# 04_-_PCIE_MINI_1_PCIE.net
KiCad netlist of a schematic drawn in Altium Designer
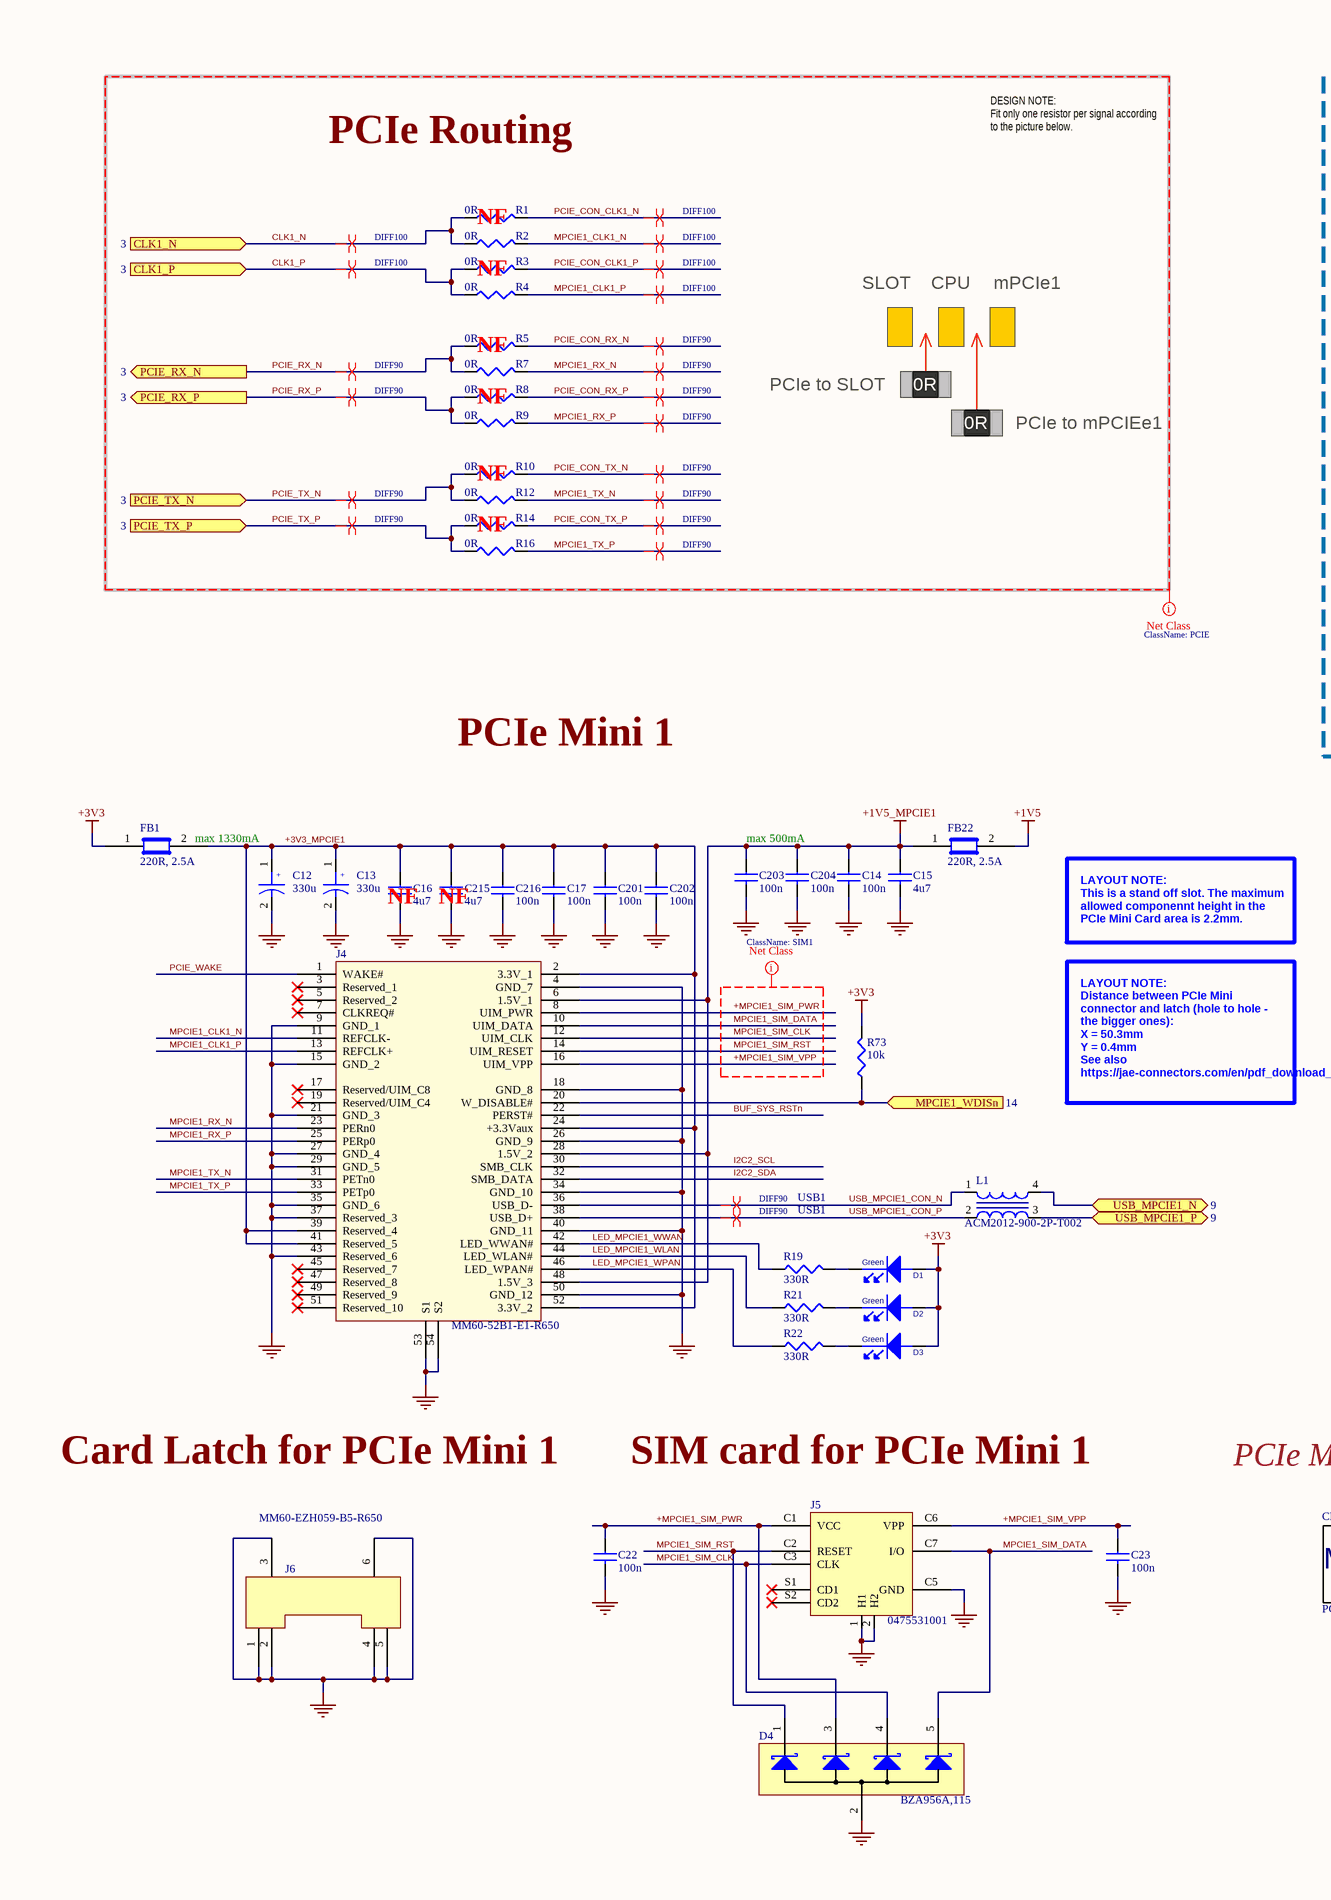
[diagram p0: [04] - PCIE MINI 1, PCIE.SchDoc, left]
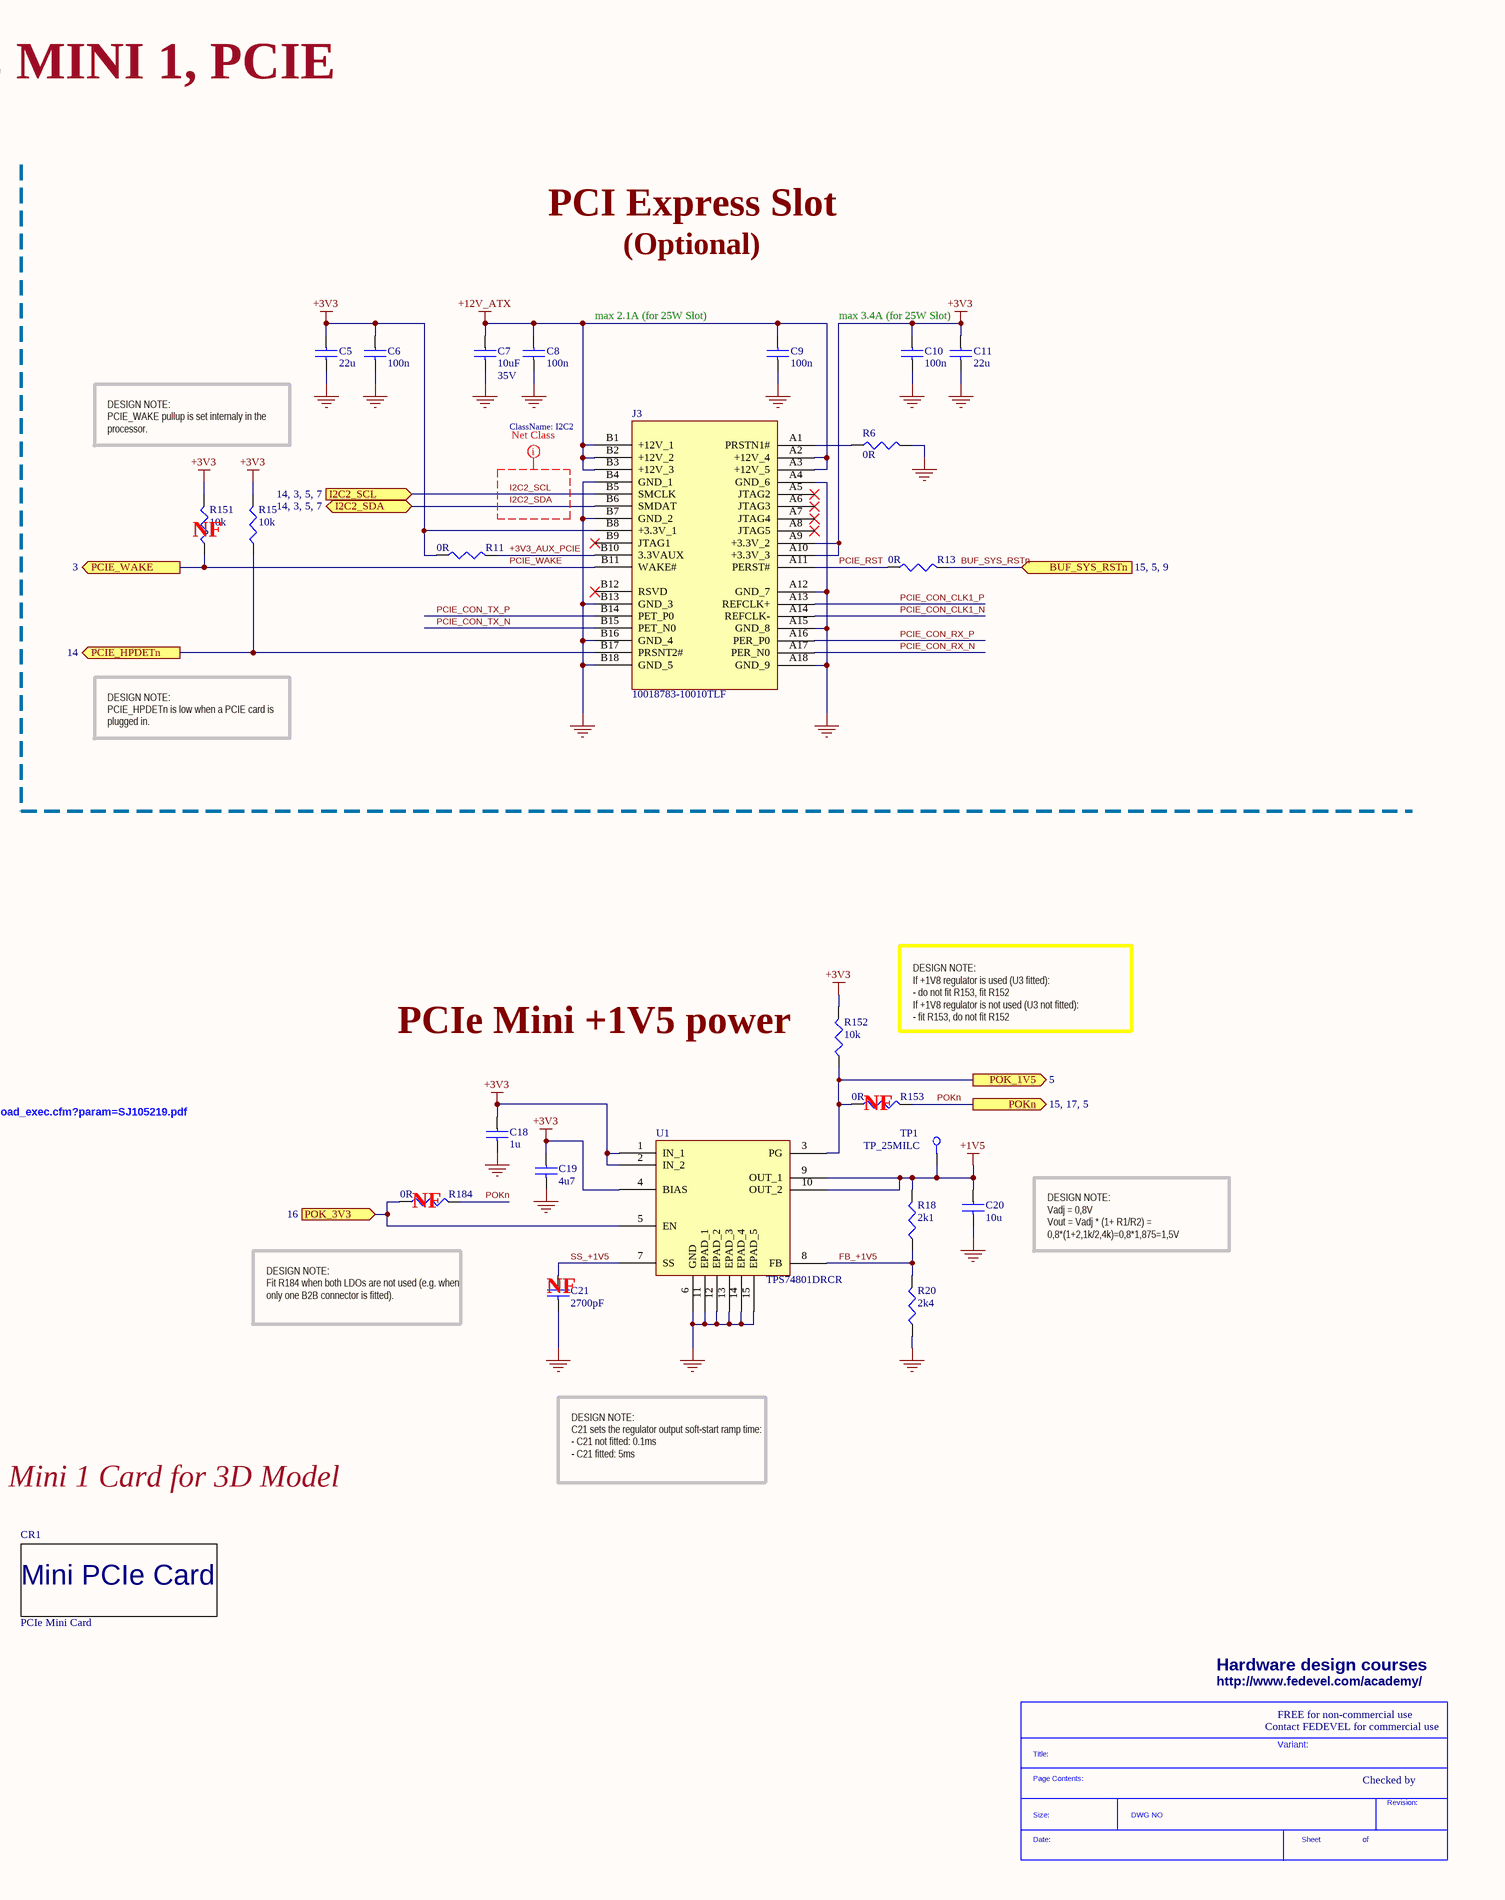
[diagram p1: [04] - PCIE MINI 1, PCIE.SchDoc, right]

(export (version "E")
  (design (tool "Eeschema 10.0.6"))
  (components
    (comp (ref "C5")
      (value "22u")
      (footprint "C0805")
      (description "CAP CER 22UF 16V 10% X5R 0805")
      (fields
        (field (name "MANUFACTURER") "TDK Corporation")
        (field (name "MANUFACTURER PART NUMBER") "C2012X5R1C226K")
        (field (name ".CHECKED PCB") "RF")
        (field (name ".CHECKED SCH") "RF")
      )
      (libsource (lib "Integrated_Library_RF_FEB_2012") (part "C2012X5R1C226K"))
    )
    (comp (ref "C6")
      (value "100n")
      (footprint "C0402")
      (description "CAP CER .10UF 50V X5R 10% 0402")
      (fields
        (field (name "MANUFACTURER") "TDK Corporation")
        (field (name "MANUFACTURER PART NUMBER") "C1005X5R1H104K")
      )
      (libsource (lib "Integrated_Library_RF_FEB_2012") (part "C1005X5R1H104K"))
    )
    (comp (ref "C7")
      (value "10uF")
      (footprint "C1206")
      (description "CAP CER 10UF 35V X5R 1206")
      (fields
        (field (name "MANUFACTURER") "Murata Electronics North America")
        (field (name "MANUFACTURER PART NUMBER") "GRM31CR6YA106KA12L")
        (field (name "VOLTAGE - RATED") "35V")
      )
      (libsource (lib "Integrated_Library_RF_FEB_2012") (part "GRM31CR6YA106KA12L"))
    )
    (comp (ref "C8")
      (value "100n")
      (footprint "C0402")
      (description "CAP CER .10UF 50V X5R 10% 0402")
      (fields
        (field (name "MANUFACTURER") "TDK Corporation")
        (field (name "MANUFACTURER PART NUMBER") "C1005X5R1H104K")
      )
      (libsource (lib "Integrated_Library_RF_FEB_2012") (part "C1005X5R1H104K"))
    )
    (comp (ref "C9")
      (value "100n")
      (footprint "C0402")
      (description "CAP CER .10UF 50V X5R 10% 0402")
      (fields
        (field (name "MANUFACTURER") "TDK Corporation")
        (field (name "MANUFACTURER PART NUMBER") "C1005X5R1H104K")
      )
      (libsource (lib "Integrated_Library_RF_FEB_2012") (part "C1005X5R1H104K"))
    )
    (comp (ref "C10")
      (value "100n")
      (footprint "C0402")
      (description "CAP CER .10UF 50V X5R 10% 0402")
      (fields
        (field (name "MANUFACTURER") "TDK Corporation")
        (field (name "MANUFACTURER PART NUMBER") "C1005X5R1H104K")
      )
      (libsource (lib "Integrated_Library_RF_FEB_2012") (part "C1005X5R1H104K"))
    )
    (comp (ref "C11")
      (value "22u")
      (footprint "C0805")
      (description "CAP CER 22UF 16V 10% X5R 0805")
      (fields
        (field (name "MANUFACTURER") "TDK Corporation")
        (field (name "MANUFACTURER PART NUMBER") "C2012X5R1C226K")
        (field (name ".CHECKED PCB") "RF")
        (field (name ".CHECKED SCH") "RF")
      )
      (libsource (lib "Integrated_Library_RF_FEB_2012") (part "C2012X5R1C226K"))
    )
    (comp (ref "C12")
      (value "330u")
      (footprint "C2917")
      (description "CAP TANT 330UF 6.3V 20% 2917")
      (fields
        (field (name "MANUFACTURER") "Kemet")
        (field (name "MANUFACTURER PART NUMBER") "T520D337M006ATE045")
        (field (name ".CREATOR") "MM")
        (field (name ".CHECKED PCB") "MM")
        (field (name ".CHECKED SCH") "RF, used by MM")
      )
      (libsource (lib "Integrated_Library_RF_FEB_2012") (part "T520D337M006ATE045"))
    )
    (comp (ref "C13")
      (value "330u")
      (footprint "C2917")
      (description "CAP TANT 330UF 6.3V 20% 2917")
      (fields
        (field (name "MANUFACTURER") "Kemet")
        (field (name "MANUFACTURER PART NUMBER") "T520D337M006ATE045")
        (field (name ".CREATOR") "MM")
        (field (name ".CHECKED PCB") "MM")
        (field (name ".CHECKED SCH") "RF, used by MM")
      )
      (libsource (lib "Integrated_Library_RF_FEB_2012") (part "T520D337M006ATE045"))
    )
    (comp (ref "C14")
      (value "100n")
      (footprint "C0402")
      (description "CAP CER .10UF 50V X5R 10% 0402")
      (fields
        (field (name "MANUFACTURER") "TDK Corporation")
        (field (name "MANUFACTURER PART NUMBER") "C1005X5R1H104K")
      )
      (libsource (lib "Integrated_Library_RF_FEB_2012") (part "C1005X5R1H104K"))
    )
    (comp (ref "C15")
      (value "4u7")
      (footprint "C0402")
      (description "CAP CER 4.7UF 10V 20% X5R 0402")
      (fields
        (field (name "MANUFACTURER") "TDK Corporation")
        (field (name "MANUFACTURER PART NUMBER") "C1005X5R1A475M")
        (field (name ".CHECKED PCB") "RF")
        (field (name ".CHECKED SCH") "RF")
      )
      (libsource (lib "Integrated_Library_RF_FEB_2012") (part "C1005X5R1A475M"))
    )
    (comp (ref "C16")
      (value "4u7")
      (footprint "C0402")
      (description "CAP CER 4.7UF 10V 20% X5R 0402")
      (fields
        (field (name "MANUFACTURER") "TDK Corporation")
        (field (name "MANUFACTURER PART NUMBER") "C1005X5R1A475M")
        (field (name ".CHECKED PCB") "RF")
        (field (name ".CHECKED SCH") "RF")
      )
      (libsource (lib "Integrated_Library_RF_FEB_2012") (part "C1005X5R1A475M"))
    )
    (comp (ref "C17")
      (value "100n")
      (footprint "C0402")
      (description "CAP CER .10UF 50V X5R 10% 0402")
      (fields
        (field (name "MANUFACTURER") "TDK Corporation")
        (field (name "MANUFACTURER PART NUMBER") "C1005X5R1H104K")
      )
      (libsource (lib "Integrated_Library_RF_FEB_2012") (part "C1005X5R1H104K"))
    )
    (comp (ref "C18")
      (value "1u")
      (footprint "C0402")
      (description "CAP CER 1.0UF 16V X5R 0402")
      (fields
        (field (name "MANUFACTURER") "TDK Corporation")
        (field (name "MANUFACTURER PART NUMBER") "C1005X5R1C105K")
      )
      (libsource (lib "Integrated_Library_RF_FEB_2012") (part "C1005X5R1C105K"))
    )
    (comp (ref "C19")
      (value "4u7")
      (footprint "C0402")
      (description "CAP CER 4.7UF 10V 20% X5R 0402")
      (fields
        (field (name "MANUFACTURER") "TDK Corporation")
        (field (name "MANUFACTURER PART NUMBER") "C1005X5R1A475M")
        (field (name ".CHECKED PCB") "RF")
        (field (name ".CHECKED SCH") "RF")
      )
      (libsource (lib "Integrated_Library_RF_FEB_2012") (part "C1005X5R1A475M"))
    )
    (comp (ref "C20")
      (value "10u")
      (footprint "C0603")
      (description "CAP CER 10UF 6.3V X5R 20% 0603")
      (fields
        (field (name "MANUFACTURER") "TDK Corporation")
        (field (name "MANUFACTURER PART NUMBER") "C1608X5R0J106M")
      )
      (libsource (lib "Integrated_Library_RF_FEB_2012") (part "C1608X5R0J106M"))
    )
    (comp (ref "C21")
      (value "2700pF")
      (footprint "C0402")
      (description "CAP CER 2700PF 50V 10% X7R 0402")
      (fields
        (field (name "MANUFACTURER") "Murata Electronics North America")
        (field (name "MANUFACTURER PART NUMBER") "GRM155R71H272KA01D")
        (field (name ".CHECKED PCB") "RF")
        (field (name ".CHECKED SCH") "RF")
      )
      (libsource (lib "Integrated_Library_RF_FEB_2012") (part "GRM155R71H272KA01D"))
    )
    (comp (ref "C22")
      (value "100n")
      (footprint "C0402")
      (description "CAP CER .10UF 50V X5R 10% 0402")
      (fields
        (field (name "MANUFACTURER") "TDK Corporation")
        (field (name "MANUFACTURER PART NUMBER") "C1005X5R1H104K")
      )
      (libsource (lib "Integrated_Library_RF_FEB_2012") (part "C1005X5R1H104K"))
    )
    (comp (ref "C23")
      (value "100n")
      (footprint "C0402")
      (description "CAP CER .10UF 50V X5R 10% 0402")
      (fields
        (field (name "MANUFACTURER") "TDK Corporation")
        (field (name "MANUFACTURER PART NUMBER") "C1005X5R1H104K")
      )
      (libsource (lib "Integrated_Library_RF_FEB_2012") (part "C1005X5R1H104K"))
    )
    (comp (ref "C201")
      (value "100n")
      (footprint "C0402")
      (description "CAP CER .10UF 50V X5R 10% 0402")
      (fields
        (field (name "MANUFACTURER") "TDK Corporation")
        (field (name "MANUFACTURER PART NUMBER") "C1005X5R1H104K")
      )
      (libsource (lib "Integrated_Library_RF_FEB_2012") (part "C1005X5R1H104K"))
    )
    (comp (ref "C202")
      (value "100n")
      (footprint "C0402")
      (description "CAP CER .10UF 50V X5R 10% 0402")
      (fields
        (field (name "MANUFACTURER") "TDK Corporation")
        (field (name "MANUFACTURER PART NUMBER") "C1005X5R1H104K")
      )
      (libsource (lib "Integrated_Library_RF_FEB_2012") (part "C1005X5R1H104K"))
    )
    (comp (ref "C203")
      (value "100n")
      (footprint "C0402")
      (description "CAP CER .10UF 50V X5R 10% 0402")
      (fields
        (field (name "MANUFACTURER") "TDK Corporation")
        (field (name "MANUFACTURER PART NUMBER") "C1005X5R1H104K")
      )
      (libsource (lib "Integrated_Library_RF_FEB_2012") (part "C1005X5R1H104K"))
    )
    (comp (ref "C204")
      (value "100n")
      (footprint "C0402")
      (description "CAP CER .10UF 50V X5R 10% 0402")
      (fields
        (field (name "MANUFACTURER") "TDK Corporation")
        (field (name "MANUFACTURER PART NUMBER") "C1005X5R1H104K")
      )
      (libsource (lib "Integrated_Library_RF_FEB_2012") (part "C1005X5R1H104K"))
    )
    (comp (ref "C215")
      (value "4u7")
      (footprint "C0402")
      (description "CAP CER 4.7UF 10V 20% X5R 0402")
      (fields
        (field (name "MANUFACTURER") "TDK Corporation")
        (field (name "MANUFACTURER PART NUMBER") "C1005X5R1A475M")
        (field (name ".CHECKED PCB") "RF")
        (field (name ".CHECKED SCH") "RF")
      )
      (libsource (lib "Integrated_Library_RF_FEB_2012") (part "C1005X5R1A475M"))
    )
    (comp (ref "C216")
      (value "100n")
      (footprint "C0402")
      (description "CAP CER .10UF 50V X5R 10% 0402")
      (fields
        (field (name "MANUFACTURER") "TDK Corporation")
        (field (name "MANUFACTURER PART NUMBER") "C1005X5R1H104K")
      )
      (libsource (lib "Integrated_Library_RF_FEB_2012") (part "C1005X5R1H104K"))
    )
    (comp (ref "CR1")
      (value "PCIe Mini Card")
      (footprint "Mini_PCIe_full card")
      (description "Card MIni PCIe")
      (fields (field (name ".CREATOR") "MM"))
      (libsource (lib "Integrated_Library_RF_FEB_2012") (part "Card_Mini_PCIe"))
    )
    (comp (ref "D1")
      (value "Green")
      (footprint "LED_0603")
      (description "LED SMARTLED GREEN 570NM 0603")
      (fields
        (field (name "MANUFACTURER") "OSRAM Opto Semiconductors Inc")
        (field (name "MANUFACTURER PART NUMBER") "LG L29K-G2J1-24-Z")
      )
      (libsource (lib "Integrated_Library_RF_FEB_2012") (part "LG L29K-G2J1-24-Z"))
    )
    (comp (ref "D2")
      (value "Green")
      (footprint "LED_0603")
      (description "LED SMARTLED GREEN 570NM 0603")
      (fields
        (field (name "MANUFACTURER") "OSRAM Opto Semiconductors Inc")
        (field (name "MANUFACTURER PART NUMBER") "LG L29K-G2J1-24-Z")
      )
      (libsource (lib "Integrated_Library_RF_FEB_2012") (part "LG L29K-G2J1-24-Z"))
    )
    (comp (ref "D3")
      (value "Green")
      (footprint "LED_0603")
      (description "LED SMARTLED GREEN 570NM 0603")
      (fields
        (field (name "MANUFACTURER") "OSRAM Opto Semiconductors Inc")
        (field (name "MANUFACTURER PART NUMBER") "LG L29K-G2J1-24-Z")
      )
      (libsource (lib "Integrated_Library_RF_FEB_2012") (part "LG L29K-G2J1-24-Z"))
    )
    (comp (ref "D4")
      (value "BZA956A,115")
      (footprint "SOT665")
      (description "TVS ZENER QUAD 5.6V SOT665")
      (fields
        (field (name "MANUFACTURER") "NXP Semiconductors")
        (field (name ".CREATOR") "MM")
        (field (name ".CHECKED PCB") "MM")
        (field (name ".CHECKED SCH") "MM")
      )
      (libsource (lib "Integrated_Library_RF_FEB_2012") (part "BZA956A,115"))
    )
    (comp (ref "FB1")
      (value "220R, 2.5A")
      (footprint "C0603")
      (description "FERRITE CHIP 220 OHM 2500MA 0603")
      (fields
        (field (name "MANUFACTURER") "Murata Electronics North America")
        (field (name "MANUFACTURER PART NUMBER") "BLM18SG221TN1D")
        (field (name ".CHECKED PCB") "RF")
        (field (name ".CHECKED SCH") "RF")
      )
      (libsource (lib "Integrated_Library_RF_FEB_2012") (part "BLM18SG221TN1D"))
    )
    (comp (ref "FB22")
      (value "220R, 2.5A")
      (footprint "C0603")
      (description "FERRITE CHIP 220 OHM 2500MA 0603")
      (fields
        (field (name "MANUFACTURER") "Murata Electronics North America")
        (field (name "MANUFACTURER PART NUMBER") "BLM18SG221TN1D")
        (field (name ".CHECKED PCB") "RF")
        (field (name ".CHECKED SCH") "RF")
      )
      (libsource (lib "Integrated_Library_RF_FEB_2012") (part "BLM18SG221TN1D"))
    )
    (comp (ref "J3")
      (value "10018783-10010TLF")
      (footprint "Mini_PCIe_36pin")
      (description "CONN PCI EXPRESS 36POS VERT PCB")
      (fields
        (field (name ".CREATOR") "MM")
        (field (name ".CHECKED PCB") "MM")
        (field (name ".CHECKED SCH") "MM")
      )
      (libsource (lib "Integrated_Library_RF_FEB_2012") (part "10018783-10010TLF"))
    )
    (comp (ref "J4")
      (value "MM60-52B1-E1-R650")
      (footprint "MINI_PCIE_52PIN_CARD_CON")
      (description "CONN MINI EXPRESS CARD 52POS SMD")
      (fields
        (field (name "MANUFACTURER") "JAE Electronics")
        (field (name ".CREATOR") "MM")
        (field (name ".CHECKED PCB") "MM")
        (field (name ".CHECKED SCH") "MM")
      )
      (libsource (lib "Integrated_Library_RF_FEB_2012") (part "MM60-52B1-E1-R650"))
    )
    (comp (ref "J5")
      (value "0475531001")
      (footprint "SIM_CARD_PUSH")
      (description "CONN CARD HOLDER SIM 6POS SMD")
      (fields
        (field (name "MANUFACTURER") "Molex Inc")
        (field (name ".CREATOR") "MM")
        (field (name ".CHECKED PCB") "MM")
        (field (name ".CHECKED SCH") "MM")
      )
      (libsource (lib "Integrated_Library_RF_FEB_2012") (part "0475531001"))
    )
    (comp (ref "J6")
      (value "MM60-EZH059-B5-R650")
      (footprint "MINI_PCIE_52PIN_CARD_LATCH")
      (description "CONN MINI EXPRESS CARD LATCH SMD")
      (fields
        (field (name "MANUFACTURER") "JAE Electronics")
        (field (name ".CREATOR") "MM")
        (field (name ".CHECKED PCB") "MM")
        (field (name ".CHECKED SCH") "MM")
      )
      (libsource (lib "Integrated_Library_RF_FEB_2012") (part "MM60-EZH059-B5-R650"))
    )
    (comp (ref "L1")
      (value "ACM2012-900-2P-T002")
      (footprint "ACM2012")
      (description "CHOKE COMM MODE 90 OHM .4A SMD")
      (fields
        (field (name "MANUFACTURER") "TDK Corporation")
        (field (name "TOLERANCE") "±1%")
        (field (name ".CHECKED PCB") "RF")
        (field (name ".CHECKED SCH") "RF")
      )
      (libsource (lib "Integrated_Library_RF_FEB_2012") (part "ACM2012-900-2P-T002"))
    )
    (comp (ref "R1")
      (value "0R")
      (footprint "R0402")
      (description "RES 0.0 OHM 1/16W 0402 SMD")
      (fields
        (field (name "MANUFACTURER") "Yageo")
        (field (name "MANUFACTURER PART NUMBER") "RC0402JR-070RL")
      )
      (libsource (lib "Integrated_Library_RF_FEB_2012") (part "RC0402JR-070RL"))
    )
    (comp (ref "R2")
      (value "0R")
      (footprint "R0402")
      (description "RES 0.0 OHM 1/16W 0402 SMD")
      (fields
        (field (name "MANUFACTURER") "Yageo")
        (field (name "MANUFACTURER PART NUMBER") "RC0402JR-070RL")
      )
      (libsource (lib "Integrated_Library_RF_FEB_2012") (part "RC0402JR-070RL"))
    )
    (comp (ref "R3")
      (value "0R")
      (footprint "R0402")
      (description "RES 0.0 OHM 1/16W 0402 SMD")
      (fields
        (field (name "MANUFACTURER") "Yageo")
        (field (name "MANUFACTURER PART NUMBER") "RC0402JR-070RL")
      )
      (libsource (lib "Integrated_Library_RF_FEB_2012") (part "RC0402JR-070RL"))
    )
    (comp (ref "R4")
      (value "0R")
      (footprint "R0402")
      (description "RES 0.0 OHM 1/16W 0402 SMD")
      (fields
        (field (name "MANUFACTURER") "Yageo")
        (field (name "MANUFACTURER PART NUMBER") "RC0402JR-070RL")
      )
      (libsource (lib "Integrated_Library_RF_FEB_2012") (part "RC0402JR-070RL"))
    )
    (comp (ref "R5")
      (value "0R")
      (footprint "R0402")
      (description "RES 0.0 OHM 1/16W 0402 SMD")
      (fields
        (field (name "MANUFACTURER") "Yageo")
        (field (name "MANUFACTURER PART NUMBER") "RC0402JR-070RL")
      )
      (libsource (lib "Integrated_Library_RF_FEB_2012") (part "RC0402JR-070RL"))
    )
    (comp (ref "R6")
      (value "0R")
      (footprint "R0402")
      (description "RES 0.0 OHM 1/16W 0402 SMD")
      (fields
        (field (name "MANUFACTURER") "Yageo")
        (field (name "MANUFACTURER PART NUMBER") "RC0402JR-070RL")
      )
      (libsource (lib "Integrated_Library_RF_FEB_2012") (part "RC0402JR-070RL"))
    )
    (comp (ref "R7")
      (value "0R")
      (footprint "R0402")
      (description "RES 0.0 OHM 1/16W 0402 SMD")
      (fields
        (field (name "MANUFACTURER") "Yageo")
        (field (name "MANUFACTURER PART NUMBER") "RC0402JR-070RL")
      )
      (libsource (lib "Integrated_Library_RF_FEB_2012") (part "RC0402JR-070RL"))
    )
    (comp (ref "R8")
      (value "0R")
      (footprint "R0402")
      (description "RES 0.0 OHM 1/16W 0402 SMD")
      (fields
        (field (name "MANUFACTURER") "Yageo")
        (field (name "MANUFACTURER PART NUMBER") "RC0402JR-070RL")
      )
      (libsource (lib "Integrated_Library_RF_FEB_2012") (part "RC0402JR-070RL"))
    )
    (comp (ref "R9")
      (value "0R")
      (footprint "R0402")
      (description "RES 0.0 OHM 1/16W 0402 SMD")
      (fields
        (field (name "MANUFACTURER") "Yageo")
        (field (name "MANUFACTURER PART NUMBER") "RC0402JR-070RL")
      )
      (libsource (lib "Integrated_Library_RF_FEB_2012") (part "RC0402JR-070RL"))
    )
    (comp (ref "R10")
      (value "0R")
      (footprint "R0402")
      (description "RES 0.0 OHM 1/16W 0402 SMD")
      (fields
        (field (name "MANUFACTURER") "Yageo")
        (field (name "MANUFACTURER PART NUMBER") "RC0402JR-070RL")
      )
      (libsource (lib "Integrated_Library_RF_FEB_2012") (part "RC0402JR-070RL"))
    )
    (comp (ref "R11")
      (value "0R")
      (footprint "R0402")
      (description "RES 0.0 OHM 1/16W 0402 SMD")
      (fields
        (field (name "MANUFACTURER") "Yageo")
        (field (name "MANUFACTURER PART NUMBER") "RC0402JR-070RL")
      )
      (libsource (lib "Integrated_Library_RF_FEB_2012") (part "RC0402JR-070RL"))
    )
    (comp (ref "R12")
      (value "0R")
      (footprint "R0402")
      (description "RES 0.0 OHM 1/16W 0402 SMD")
      (fields
        (field (name "MANUFACTURER") "Yageo")
        (field (name "MANUFACTURER PART NUMBER") "RC0402JR-070RL")
      )
      (libsource (lib "Integrated_Library_RF_FEB_2012") (part "RC0402JR-070RL"))
    )
    (comp (ref "R13")
      (value "0R")
      (footprint "R0402")
      (description "RES 0.0 OHM 1/16W 0402 SMD")
      (fields
        (field (name "MANUFACTURER") "Yageo")
        (field (name "MANUFACTURER PART NUMBER") "RC0402JR-070RL")
      )
      (libsource (lib "Integrated_Library_RF_FEB_2012") (part "RC0402JR-070RL"))
    )
    (comp (ref "R14")
      (value "0R")
      (footprint "R0402")
      (description "RES 0.0 OHM 1/16W 0402 SMD")
      (fields
        (field (name "MANUFACTURER") "Yageo")
        (field (name "MANUFACTURER PART NUMBER") "RC0402JR-070RL")
      )
      (libsource (lib "Integrated_Library_RF_FEB_2012") (part "RC0402JR-070RL"))
    )
    (comp (ref "R15")
      (value "10k")
      (footprint "R0402")
      (description "RES 10.0K OHM 1/16W 1% 0402 SMD")
      (fields
        (field (name "MANUFACTURER") "Yageo")
        (field (name "MANUFACTURER PART NUMBER") "RC0402FR-0710KL")
      )
      (libsource (lib "Integrated_Library_RF_FEB_2012") (part "RC0402FR-0710KL"))
    )
    (comp (ref "R16")
      (value "0R")
      (footprint "R0402")
      (description "RES 0.0 OHM 1/16W 0402 SMD")
      (fields
        (field (name "MANUFACTURER") "Yageo")
        (field (name "MANUFACTURER PART NUMBER") "RC0402JR-070RL")
      )
      (libsource (lib "Integrated_Library_RF_FEB_2012") (part "RC0402JR-070RL"))
    )
    (comp (ref "R18")
      (value "2k1")
      (footprint "R0402")
      (description "RES 2.10K OHM 1/16W 1% 0402 SMD")
      (fields
        (field (name "MANUFACTURER") "Vishay Dale")
        (field (name "MANUFACTURER PART NUMBER") "CRCW04022K10FKED")
        (field (name ".CREATOR") "MM")
        (field (name ".CHECKED PCB") "RF, used by MM")
        (field (name ".CHECKED SCH") "RF, used by MM")
      )
      (libsource (lib "Integrated_Library_RF_FEB_2012") (part "CRCW04022K10FKED"))
    )
    (comp (ref "R19")
      (value "330R")
      (footprint "R0402")
      (description "RES 330 OHM 1/16W 1% 0402 SMD")
      (fields
        (field (name "MANUFACTURER") "Vishay Dale")
        (field (name "MANUFACTURER PART NUMBER") "CRCW0402330RFKED")
        (field (name ".CHECKED PCB") "RF")
        (field (name ".CHECKED SCH") "RF")
      )
      (libsource (lib "Integrated_Library_RF_FEB_2012") (part "CRCW0402330RFKED"))
    )
    (comp (ref "R20")
      (value "2k4")
      (footprint "R0402")
      (description "RES 2.40K OHM 1/16W 1% 0402 SMD")
      (fields
        (field (name "MANUFACTURER") "Vishay Dale")
        (field (name "MANUFACTURER PART NUMBER") "CRCW04022K40FKED")
        (field (name ".CHECKED PCB") "RF")
        (field (name ".CHECKED SCH") "RF")
      )
      (libsource (lib "Integrated_Library_RF_FEB_2012") (part "CRCW04022K40FKED"))
    )
    (comp (ref "R21")
      (value "330R")
      (footprint "R0402")
      (description "RES 330 OHM 1/16W 1% 0402 SMD")
      (fields
        (field (name "MANUFACTURER") "Vishay Dale")
        (field (name "MANUFACTURER PART NUMBER") "CRCW0402330RFKED")
        (field (name ".CHECKED PCB") "RF")
        (field (name ".CHECKED SCH") "RF")
      )
      (libsource (lib "Integrated_Library_RF_FEB_2012") (part "CRCW0402330RFKED"))
    )
    (comp (ref "R22")
      (value "330R")
      (footprint "R0402")
      (description "RES 330 OHM 1/16W 1% 0402 SMD")
      (fields
        (field (name "MANUFACTURER") "Vishay Dale")
        (field (name "MANUFACTURER PART NUMBER") "CRCW0402330RFKED")
        (field (name ".CHECKED PCB") "RF")
        (field (name ".CHECKED SCH") "RF")
      )
      (libsource (lib "Integrated_Library_RF_FEB_2012") (part "CRCW0402330RFKED"))
    )
    (comp (ref "R73")
      (value "10k")
      (footprint "R0402")
      (description "RES 10.0K OHM 1/16W 1% 0402 SMD")
      (fields
        (field (name "MANUFACTURER") "Yageo")
        (field (name "MANUFACTURER PART NUMBER") "RC0402FR-0710KL")
      )
      (libsource (lib "Integrated_Library_RF_FEB_2012") (part "RC0402FR-0710KL"))
    )
    (comp (ref "R151")
      (value "10k")
      (footprint "R0402")
      (description "RES 10.0K OHM 1/16W 1% 0402 SMD")
      (fields
        (field (name "MANUFACTURER") "Yageo")
        (field (name "MANUFACTURER PART NUMBER") "RC0402FR-0710KL")
      )
      (libsource (lib "Integrated_Library_RF_FEB_2012") (part "RC0402FR-0710KL"))
    )
    (comp (ref "R152")
      (value "10k")
      (footprint "R0402")
      (description "RES 10.0K OHM 1/16W 1% 0402 SMD")
      (fields
        (field (name "MANUFACTURER") "Yageo")
        (field (name "MANUFACTURER PART NUMBER") "RC0402FR-0710KL")
      )
      (libsource (lib "Integrated_Library_RF_FEB_2012") (part "RC0402FR-0710KL"))
    )
    (comp (ref "R153")
      (value "0R")
      (footprint "R0402")
      (description "RES 0.0 OHM 1/16W 0402 SMD")
      (fields
        (field (name "MANUFACTURER") "Yageo")
        (field (name "MANUFACTURER PART NUMBER") "RC0402JR-070RL")
      )
      (libsource (lib "Integrated_Library_RF_FEB_2012") (part "RC0402JR-070RL"))
    )
    (comp (ref "R184")
      (value "0R")
      (footprint "R0402")
      (description "RES 0.0 OHM 1/16W 0402 SMD")
      (fields
        (field (name "MANUFACTURER") "Yageo")
        (field (name "MANUFACTURER PART NUMBER") "RC0402JR-070RL")
      )
      (libsource (lib "Integrated_Library_RF_FEB_2012") (part "RC0402JR-070RL"))
    )
    (comp (ref "TP1")
      (value "TP_25MILC")
      (footprint "TP_25C")
      (description "Test Point 25mil")
      (libsource (lib "Integrated_Library_RF_FEB_2012") (part "TP_25MILC"))
    )
    (comp (ref "U1")
      (value "TPS74801DRCR")
      (footprint "DRC (S-PVSON-N10)")
      (description "IC REG LDO ADJ 1.5A 10SON")
      (fields
        (field (name "MANUFACTURER") "Texas Instruments")
        (field (name ".CREATOR") "MM")
        (field (name ".CHECKED PCB") "RF, used by MM")
        (field (name ".CHECKED SCH") "MM")
      )
      (libsource (lib "Integrated_Library_RF_FEB_2012") (part "TPS74801DRCR"))
    )
  )
  (nets
    (net (code "1") (name "+1V5") (class "Default")
      (node (ref "C20") (pin "1") (pinfunction "1_1") (pintype "passive"))
      (node (ref "FB22") (pin "2") (pinfunction "2_2") (pintype "passive"))
      (node (ref "R18") (pin "2") (pinfunction "2_2") (pintype "passive"))
      (node (ref "TP1") (pin "1") (pinfunction "1_1") (pintype "passive"))
      (node (ref "U1") (pin "10") (pinfunction "OUT_2_10") (pintype "passive"))
      (node (ref "U1") (pin "9") (pinfunction "OUT_1_9") (pintype "passive"))
    )
    (net (code "2") (name "+1V5_MPCIE1") (class "Default")
      (node (ref "C14") (pin "1") (pinfunction "1_1") (pintype "passive"))
      (node (ref "C15") (pin "1") (pinfunction "1_1") (pintype "passive"))
      (node (ref "C203") (pin "1") (pinfunction "1_1") (pintype "passive"))
      (node (ref "C204") (pin "1") (pinfunction "1_1") (pintype "passive"))
      (node (ref "FB22") (pin "1") (pinfunction "1_1") (pintype "passive"))
      (node (ref "J4") (pin "28") (pinfunction "1.5V_2_28") (pintype "passive"))
      (node (ref "J4") (pin "48") (pinfunction "1.5V_3_48") (pintype "passive"))
      (node (ref "J4") (pin "6") (pinfunction "1.5V_1_6") (pintype "passive"))
    )
    (net (code "3") (name "+3V3") (class "Default")
      (node (ref "C10") (pin "1") (pinfunction "1_1") (pintype "passive"))
      (node (ref "C11") (pin "1") (pinfunction "1_1") (pintype "passive"))
      (node (ref "C18") (pin "1") (pinfunction "1_1") (pintype "passive"))
      (node (ref "C19") (pin "1") (pinfunction "1_1") (pintype "passive"))
      (node (ref "C5") (pin "1") (pinfunction "1_1") (pintype "passive"))
      (node (ref "C6") (pin "1") (pinfunction "1_1") (pintype "passive"))
      (node (ref "D1") (pin "2") (pinfunction "ANODE_2") (pintype "passive"))
      (node (ref "D2") (pin "2") (pinfunction "ANODE_2") (pintype "passive"))
      (node (ref "D3") (pin "2") (pinfunction "ANODE_2") (pintype "passive"))
      (node (ref "FB1") (pin "1") (pinfunction "1_1") (pintype "passive"))
      (node (ref "J3") (pin "A10") (pinfunction "+3.3V_3_A10") (pintype "passive"))
      (node (ref "J3") (pin "A9") (pinfunction "+3.3V_2_A9") (pintype "passive"))
      (node (ref "J3") (pin "B8") (pinfunction "+3.3V_1_B8") (pintype "passive"))
      (node (ref "R11") (pin "1") (pinfunction "1_1") (pintype "passive"))
      (node (ref "R15") (pin "2") (pinfunction "2_2") (pintype "passive"))
      (node (ref "R151") (pin "2") (pinfunction "2_2") (pintype "passive"))
      (node (ref "R152") (pin "2") (pinfunction "2_2") (pintype "passive"))
      (node (ref "R73") (pin "2") (pinfunction "2_2") (pintype "passive"))
      (node (ref "U1") (pin "1") (pinfunction "IN_1_1") (pintype "passive"))
      (node (ref "U1") (pin "2") (pinfunction "IN_2_2") (pintype "passive"))
      (node (ref "U1") (pin "4") (pinfunction "BIAS_4") (pintype "passive"))
    )
    (net (code "4") (name "+12V_ATX") (class "Default")
      (node (ref "C7") (pin "1") (pinfunction "1_1") (pintype "passive"))
      (node (ref "C8") (pin "1") (pinfunction "1_1") (pintype "passive"))
      (node (ref "C9") (pin "1") (pinfunction "1_1") (pintype "passive"))
      (node (ref "J3") (pin "A2") (pinfunction "+12V_4_A2") (pintype "passive"))
      (node (ref "J3") (pin "A3") (pinfunction "+12V_5_A3") (pintype "passive"))
      (node (ref "J3") (pin "B1") (pinfunction "+12V_1_B1") (pintype "passive"))
      (node (ref "J3") (pin "B2") (pinfunction "+12V_2_B2") (pintype "passive"))
      (node (ref "J3") (pin "B3") (pinfunction "+12V_3_B3") (pintype "passive"))
    )
    (net (code "5") (name "/+3V3_AUX_PCIE") (class "Default")
      (node (ref "J3") (pin "B10") (pinfunction "3.3VAUX_B10") (pintype "passive"))
      (node (ref "R11") (pin "2") (pinfunction "2_2") (pintype "passive"))
    )
    (net (code "6") (name "/+3V3_MPCIE1") (class "Default")
      (node (ref "C12") (pin "1") (pinfunction "1_1") (pintype "passive"))
      (node (ref "C13") (pin "1") (pinfunction "1_1") (pintype "passive"))
      (node (ref "C16") (pin "1") (pinfunction "1_1") (pintype "passive"))
      (node (ref "C17") (pin "1") (pinfunction "1_1") (pintype "passive"))
      (node (ref "C201") (pin "1") (pinfunction "1_1") (pintype "passive"))
      (node (ref "C202") (pin "1") (pinfunction "1_1") (pintype "passive"))
      (node (ref "C215") (pin "1") (pinfunction "1_1") (pintype "passive"))
      (node (ref "C216") (pin "1") (pinfunction "1_1") (pintype "passive"))
      (node (ref "FB1") (pin "2") (pinfunction "2_2") (pintype "passive"))
      (node (ref "J4") (pin "2") (pinfunction "3.3V_1_2") (pintype "passive"))
      (node (ref "J4") (pin "24") (pinfunction "+3.3Vaux_24") (pintype "passive"))
      (node (ref "J4") (pin "39") (pinfunction "Reserved_4_39") (pintype "passive"))
      (node (ref "J4") (pin "41") (pinfunction "Reserved_5_41") (pintype "passive"))
      (node (ref "J4") (pin "52") (pinfunction "3.3V_2_52") (pintype "passive"))
    )
    (net (code "7") (name "/+MPCIE1_SIM_PWR") (class "Default")
      (node (ref "C22") (pin "1") (pinfunction "1_1") (pintype "passive"))
      (node (ref "D4") (pin "3") (pinfunction "3_3") (pintype "passive"))
      (node (ref "J4") (pin "8") (pinfunction "UIM_PWR_8") (pintype "passive"))
      (node (ref "J5") (pin "C1") (pinfunction "VCC_C1") (pintype "passive"))
    )
    (net (code "8") (name "/+MPCIE1_SIM_VPP") (class "Default")
      (node (ref "C23") (pin "1") (pinfunction "1_1") (pintype "passive"))
      (node (ref "J4") (pin "16") (pinfunction "UIM_VPP_16") (pintype "passive"))
      (node (ref "J5") (pin "C6") (pinfunction "VPP_C6") (pintype "passive"))
    )
    (net (code "9") (name "/BUF_SYS_RSTn") (class "Default")
      (node (ref "J4") (pin "22") (pinfunction "PERST#_22") (pintype "passive"))
      (node (ref "R13") (pin "2") (pinfunction "2_2") (pintype "passive"))
    )
    (net (code "10") (name "/CLK1_N") (class "Default")
      (node (ref "R1") (pin "1") (pinfunction "1_1") (pintype "passive"))
      (node (ref "R2") (pin "1") (pinfunction "1_1") (pintype "passive"))
    )
    (net (code "11") (name "/CLK1_P") (class "Default")
      (node (ref "R3") (pin "1") (pinfunction "1_1") (pintype "passive"))
      (node (ref "R4") (pin "1") (pinfunction "1_1") (pintype "passive"))
    )
    (net (code "12") (name "/FB_+1V5") (class "Default")
      (node (ref "R18") (pin "1") (pinfunction "1_1") (pintype "passive"))
      (node (ref "R20") (pin "2") (pinfunction "2_2") (pintype "passive"))
      (node (ref "U1") (pin "8") (pinfunction "FB_8") (pintype "passive"))
    )
    (net (code "13") (name "/I2C2_SCL") (class "Default")
      (node (ref "J3") (pin "B5") (pinfunction "SMCLK_B5") (pintype "passive"))
      (node (ref "J4") (pin "30") (pinfunction "SMB_CLK_30") (pintype "passive"))
    )
    (net (code "14") (name "/I2C2_SDA") (class "Default")
      (node (ref "J3") (pin "B6") (pinfunction "SMDAT_B6") (pintype "passive"))
      (node (ref "J4") (pin "32") (pinfunction "SMB_DATA_32") (pintype "passive"))
    )
    (net (code "15") (name "/LED_MPCIE1_WLAN") (class "Default")
      (node (ref "J4") (pin "44") (pinfunction "LED_WLAN#_44") (pintype "passive"))
      (node (ref "R21") (pin "1") (pinfunction "1_1") (pintype "passive"))
    )
    (net (code "16") (name "/LED_MPCIE1_WPAN") (class "Default")
      (node (ref "J4") (pin "46") (pinfunction "LED_WPAN#_46") (pintype "passive"))
      (node (ref "R22") (pin "1") (pinfunction "1_1") (pintype "passive"))
    )
    (net (code "17") (name "/LED_MPCIE1_WWAN") (class "Default")
      (node (ref "J4") (pin "42") (pinfunction "LED_WWAN#_42") (pintype "passive"))
      (node (ref "R19") (pin "1") (pinfunction "1_1") (pintype "passive"))
    )
    (net (code "18") (name "/MPCIE1_CLK1_N") (class "Default")
      (node (ref "J4") (pin "11") (pinfunction "REFCLK-_11") (pintype "passive"))
      (node (ref "R2") (pin "2") (pinfunction "2_2") (pintype "passive"))
    )
    (net (code "19") (name "/MPCIE1_CLK1_P") (class "Default")
      (node (ref "J4") (pin "13") (pinfunction "REFCLK+_13") (pintype "passive"))
      (node (ref "R4") (pin "2") (pinfunction "2_2") (pintype "passive"))
    )
    (net (code "20") (name "/MPCIE1_RX_N") (class "Default")
      (node (ref "J4") (pin "23") (pinfunction "PERn0_23") (pintype "passive"))
      (node (ref "R7") (pin "2") (pinfunction "2_2") (pintype "passive"))
    )
    (net (code "21") (name "/MPCIE1_RX_P") (class "Default")
      (node (ref "J4") (pin "25") (pinfunction "PERp0_25") (pintype "passive"))
      (node (ref "R9") (pin "2") (pinfunction "2_2") (pintype "passive"))
    )
    (net (code "22") (name "/MPCIE1_SIM_CLK") (class "Default")
      (node (ref "D4") (pin "4") (pinfunction "4_4") (pintype "passive"))
      (node (ref "J4") (pin "12") (pinfunction "UIM_CLK_12") (pintype "passive"))
      (node (ref "J5") (pin "C3") (pinfunction "CLK_C3") (pintype "passive"))
    )
    (net (code "23") (name "/MPCIE1_SIM_DATA") (class "Default")
      (node (ref "D4") (pin "5") (pinfunction "5_5") (pintype "passive"))
      (node (ref "J4") (pin "10") (pinfunction "UIM_DATA_10") (pintype "passive"))
      (node (ref "J5") (pin "C7") (pinfunction "I/O_C7") (pintype "passive"))
    )
    (net (code "24") (name "/MPCIE1_SIM_RST") (class "Default")
      (node (ref "D4") (pin "1") (pinfunction "1_1") (pintype "passive"))
      (node (ref "J4") (pin "14") (pinfunction "UIM_RESET_14") (pintype "passive"))
      (node (ref "J5") (pin "C2") (pinfunction "RESET_C2") (pintype "passive"))
    )
    (net (code "25") (name "/MPCIE1_TX_N") (class "Default")
      (node (ref "J4") (pin "31") (pinfunction "PETn0_31") (pintype "passive"))
      (node (ref "R12") (pin "2") (pinfunction "2_2") (pintype "passive"))
    )
    (net (code "26") (name "/MPCIE1_TX_P") (class "Default")
      (node (ref "J4") (pin "33") (pinfunction "PETp0_33") (pintype "passive"))
      (node (ref "R16") (pin "2") (pinfunction "2_2") (pintype "passive"))
    )
    (net (code "27") (name "/MPCIE1_WDISn") (class "Default")
      (node (ref "J4") (pin "20") (pinfunction "W_DISABLE#_20") (pintype "passive"))
      (node (ref "R73") (pin "1") (pinfunction "1_1") (pintype "passive"))
    )
    (net (code "28") (name "/PCIE_CON_CLK1_N") (class "Default")
      (node (ref "J3") (pin "A14") (pinfunction "REFCLK-_A14") (pintype "passive"))
      (node (ref "R1") (pin "2") (pinfunction "2_2") (pintype "passive"))
    )
    (net (code "29") (name "/PCIE_CON_CLK1_P") (class "Default")
      (node (ref "J3") (pin "A13") (pinfunction "REFCLK+_A13") (pintype "passive"))
      (node (ref "R3") (pin "2") (pinfunction "2_2") (pintype "passive"))
    )
    (net (code "30") (name "/PCIE_CON_RX_N") (class "Default")
      (node (ref "J3") (pin "A17") (pinfunction "PER_N0_A17") (pintype "passive"))
      (node (ref "R5") (pin "2") (pinfunction "2_2") (pintype "passive"))
    )
    (net (code "31") (name "/PCIE_CON_RX_P") (class "Default")
      (node (ref "J3") (pin "A16") (pinfunction "PER_P0_A16") (pintype "passive"))
      (node (ref "R8") (pin "2") (pinfunction "2_2") (pintype "passive"))
    )
    (net (code "32") (name "/PCIE_CON_TX_N") (class "Default")
      (node (ref "J3") (pin "B15") (pinfunction "PET_N0_B15") (pintype "passive"))
      (node (ref "R10") (pin "2") (pinfunction "2_2") (pintype "passive"))
    )
    (net (code "33") (name "/PCIE_CON_TX_P") (class "Default")
      (node (ref "J3") (pin "B14") (pinfunction "PET_P0_B14") (pintype "passive"))
      (node (ref "R14") (pin "2") (pinfunction "2_2") (pintype "passive"))
    )
    (net (code "34") (name "/PCIE_HPDETn") (class "Default")
      (node (ref "J3") (pin "B17") (pinfunction "PRSNT2#_B17") (pintype "passive"))
      (node (ref "R15") (pin "1") (pinfunction "1_1") (pintype "passive"))
    )
    (net (code "35") (name "/PCIE_RST") (class "Default")
      (node (ref "J3") (pin "A11") (pinfunction "PERST#_A11") (pintype "passive"))
      (node (ref "R13") (pin "1") (pinfunction "1_1") (pintype "passive"))
    )
    (net (code "36") (name "/PCIE_RX_N") (class "Default")
      (node (ref "R5") (pin "1") (pinfunction "1_1") (pintype "passive"))
      (node (ref "R7") (pin "1") (pinfunction "1_1") (pintype "passive"))
    )
    (net (code "37") (name "/PCIE_RX_P") (class "Default")
      (node (ref "R8") (pin "1") (pinfunction "1_1") (pintype "passive"))
      (node (ref "R9") (pin "1") (pinfunction "1_1") (pintype "passive"))
    )
    (net (code "38") (name "/PCIE_TX_N") (class "Default")
      (node (ref "R10") (pin "1") (pinfunction "1_1") (pintype "passive"))
      (node (ref "R12") (pin "1") (pinfunction "1_1") (pintype "passive"))
    )
    (net (code "39") (name "/PCIE_TX_P") (class "Default")
      (node (ref "R14") (pin "1") (pinfunction "1_1") (pintype "passive"))
      (node (ref "R16") (pin "1") (pinfunction "1_1") (pintype "passive"))
    )
    (net (code "40") (name "/PCIE_WAKE") (class "Default")
      (node (ref "J3") (pin "B11") (pinfunction "WAKE#_B11") (pintype "passive"))
      (node (ref "J4") (pin "1") (pinfunction "WAKE#_1") (pintype "passive"))
      (node (ref "R151") (pin "1") (pinfunction "1_1") (pintype "passive"))
    )
    (net (code "41") (name "/POK_1V5") (class "Default")
      (node (ref "R152") (pin "1") (pinfunction "1_1") (pintype "passive"))
      (node (ref "R153") (pin "1") (pinfunction "1_1") (pintype "passive"))
      (node (ref "U1") (pin "3") (pinfunction "PG_3") (pintype "passive"))
    )
    (net (code "42") (name "/POK_3V3") (class "Default")
      (node (ref "R184") (pin "1") (pinfunction "1_1") (pintype "passive"))
      (node (ref "U1") (pin "5") (pinfunction "EN_5") (pintype "passive"))
    )
    (net (code "43") (name "/POKn") (class "Default")
      (node (ref "R153") (pin "2") (pinfunction "2_2") (pintype "passive"))
      (node (ref "R184") (pin "2") (pinfunction "2_2") (pintype "passive"))
    )
    (net (code "44") (name "/SS_+1V5") (class "Default")
      (node (ref "C21") (pin "1") (pinfunction "1_1") (pintype "passive"))
      (node (ref "U1") (pin "7") (pinfunction "SS_7") (pintype "passive"))
    )
    (net (code "45") (name "/USB_MPCIE1_CON_N") (class "Default")
      (node (ref "J4") (pin "36") (pinfunction "USB_D-_36") (pintype "passive"))
      (node (ref "L1") (pin "1") (pinfunction "1_1") (pintype "passive"))
    )
    (net (code "46") (name "/USB_MPCIE1_CON_P") (class "Default")
      (node (ref "J4") (pin "38") (pinfunction "USB_D+_38") (pintype "passive"))
      (node (ref "L1") (pin "2") (pinfunction "2_2") (pintype "passive"))
    )
    (net (code "47") (name "/USB_MPCIE1_N") (class "Default")
      (node (ref "L1") (pin "4") (pinfunction "4_4") (pintype "passive"))
    )
    (net (code "48") (name "/USB_MPCIE1_P") (class "Default")
      (node (ref "L1") (pin "3") (pinfunction "3_3") (pintype "passive"))
    )
    (net (code "49") (name "GND") (class "Default")
      (node (ref "C10") (pin "2") (pinfunction "2_2") (pintype "passive"))
      (node (ref "C11") (pin "2") (pinfunction "2_2") (pintype "passive"))
      (node (ref "C12") (pin "2") (pinfunction "2_2") (pintype "passive"))
      (node (ref "C13") (pin "2") (pinfunction "2_2") (pintype "passive"))
      (node (ref "C14") (pin "2") (pinfunction "2_2") (pintype "passive"))
      (node (ref "C15") (pin "2") (pinfunction "2_2") (pintype "passive"))
      (node (ref "C16") (pin "2") (pinfunction "2_2") (pintype "passive"))
      (node (ref "C17") (pin "2") (pinfunction "2_2") (pintype "passive"))
      (node (ref "C18") (pin "2") (pinfunction "2_2") (pintype "passive"))
      (node (ref "C19") (pin "2") (pinfunction "2_2") (pintype "passive"))
      (node (ref "C20") (pin "2") (pinfunction "2_2") (pintype "passive"))
      (node (ref "C201") (pin "2") (pinfunction "2_2") (pintype "passive"))
      (node (ref "C202") (pin "2") (pinfunction "2_2") (pintype "passive"))
      (node (ref "C203") (pin "2") (pinfunction "2_2") (pintype "passive"))
      (node (ref "C204") (pin "2") (pinfunction "2_2") (pintype "passive"))
      (node (ref "C21") (pin "2") (pinfunction "2_2") (pintype "passive"))
      (node (ref "C215") (pin "2") (pinfunction "2_2") (pintype "passive"))
      (node (ref "C216") (pin "2") (pinfunction "2_2") (pintype "passive"))
      (node (ref "C22") (pin "2") (pinfunction "2_2") (pintype "passive"))
      (node (ref "C23") (pin "2") (pinfunction "2_2") (pintype "passive"))
      (node (ref "C5") (pin "2") (pinfunction "2_2") (pintype "passive"))
      (node (ref "C6") (pin "2") (pinfunction "2_2") (pintype "passive"))
      (node (ref "C7") (pin "2") (pinfunction "2_2") (pintype "passive"))
      (node (ref "C8") (pin "2") (pinfunction "2_2") (pintype "passive"))
      (node (ref "C9") (pin "2") (pinfunction "2_2") (pintype "passive"))
      (node (ref "D4") (pin "2") (pinfunction "2_2") (pintype "passive"))
      (node (ref "J3") (pin "A12") (pinfunction "GND_7_A12") (pintype "passive"))
      (node (ref "J3") (pin "A15") (pinfunction "GND_8_A15") (pintype "passive"))
      (node (ref "J3") (pin "A18") (pinfunction "GND_9_A18") (pintype "passive"))
      (node (ref "J3") (pin "A4") (pinfunction "GND_6_A4") (pintype "passive"))
      (node (ref "J3") (pin "B13") (pinfunction "GND_3_B13") (pintype "passive"))
      (node (ref "J3") (pin "B16") (pinfunction "GND_4_B16") (pintype "passive"))
      (node (ref "J3") (pin "B18") (pinfunction "GND_5_B18") (pintype "passive"))
      (node (ref "J3") (pin "B4") (pinfunction "GND_1_B4") (pintype "passive"))
      (node (ref "J3") (pin "B7") (pinfunction "GND_2_B7") (pintype "passive"))
      (node (ref "J4") (pin "15") (pinfunction "GND_2_15") (pintype "passive"))
      (node (ref "J4") (pin "18") (pinfunction "GND_8_18") (pintype "passive"))
      (node (ref "J4") (pin "21") (pinfunction "GND_3_21") (pintype "passive"))
      (node (ref "J4") (pin "26") (pinfunction "GND_9_26") (pintype "passive"))
      (node (ref "J4") (pin "27") (pinfunction "GND_4_27") (pintype "passive"))
      (node (ref "J4") (pin "29") (pinfunction "GND_5_29") (pintype "passive"))
      (node (ref "J4") (pin "34") (pinfunction "GND_10_34") (pintype "passive"))
      (node (ref "J4") (pin "35") (pinfunction "GND_6_35") (pintype "passive"))
      (node (ref "J4") (pin "37") (pinfunction "Reserved_3_37") (pintype "passive"))
      (node (ref "J4") (pin "4") (pinfunction "GND_7_4") (pintype "passive"))
      (node (ref "J4") (pin "40") (pinfunction "GND_11_40") (pintype "passive"))
      (node (ref "J4") (pin "43") (pinfunction "Reserved_6_43") (pintype "passive"))
      (node (ref "J4") (pin "50") (pinfunction "GND_12_50") (pintype "passive"))
      (node (ref "J4") (pin "53") (pinfunction "S1_53") (pintype "passive"))
      (node (ref "J4") (pin "54") (pinfunction "S2_54") (pintype "passive"))
      (node (ref "J4") (pin "9") (pinfunction "GND_1_9") (pintype "passive"))
      (node (ref "J5") (pin "1") (pinfunction "H1_1") (pintype "passive"))
      (node (ref "J5") (pin "2") (pinfunction "H2_2") (pintype "passive"))
      (node (ref "J5") (pin "C5") (pinfunction "GND_C5") (pintype "passive"))
      (node (ref "J6") (pin "1") (pinfunction "1_1") (pintype "passive"))
      (node (ref "J6") (pin "2") (pinfunction "2_2") (pintype "passive"))
      (node (ref "J6") (pin "3") (pinfunction "3_3") (pintype "passive"))
      (node (ref "J6") (pin "4") (pinfunction "4_4") (pintype "passive"))
      (node (ref "J6") (pin "5") (pinfunction "5_5") (pintype "passive"))
      (node (ref "J6") (pin "6") (pinfunction "6_6") (pintype "passive"))
      (node (ref "R20") (pin "1") (pinfunction "1_1") (pintype "passive"))
      (node (ref "R6") (pin "2") (pinfunction "2_2") (pintype "passive"))
      (node (ref "U1") (pin "11") (pinfunction "EPAD_1_11") (pintype "passive"))
      (node (ref "U1") (pin "12") (pinfunction "EPAD_2_12") (pintype "passive"))
      (node (ref "U1") (pin "13") (pinfunction "EPAD_3_13") (pintype "passive"))
      (node (ref "U1") (pin "14") (pinfunction "EPAD_4_14") (pintype "passive"))
      (node (ref "U1") (pin "15") (pinfunction "EPAD_5_15") (pintype "passive"))
      (node (ref "U1") (pin "6") (pinfunction "GND_6") (pintype "passive"))
    )
    (net (code "50") (name "Net-(D1-cathode)") (class "Default")
      (node (ref "D1") (pin "1") (pinfunction "cathode_1") (pintype "passive"))
      (node (ref "R19") (pin "2") (pinfunction "2_2") (pintype "passive"))
    )
    (net (code "51") (name "Net-(D2-cathode)") (class "Default")
      (node (ref "D2") (pin "1") (pinfunction "cathode_1") (pintype "passive"))
      (node (ref "R21") (pin "2") (pinfunction "2_2") (pintype "passive"))
    )
    (net (code "52") (name "Net-(D3-cathode)") (class "Default")
      (node (ref "D3") (pin "1") (pinfunction "cathode_1") (pintype "passive"))
      (node (ref "R22") (pin "2") (pinfunction "2_2") (pintype "passive"))
    )
    (net (code "53") (name "Net-(J3-PRSTN1#)") (class "Default")
      (node (ref "J3") (pin "A1") (pinfunction "PRSTN1#_A1") (pintype "passive"))
      (node (ref "R6") (pin "1") (pinfunction "1_1") (pintype "passive"))
    )
    (net (code "54") (name "unconnected-(J3-JTAG1-PadB9)") (class "Default")
      (node (ref "J3") (pin "B9") (pinfunction "JTAG1_B9") (pintype "passive+no_connect"))
    )
    (net (code "55") (name "unconnected-(J3-JTAG2-PadA5)") (class "Default")
      (node (ref "J3") (pin "A5") (pinfunction "JTAG2_A5") (pintype "passive+no_connect"))
    )
    (net (code "56") (name "unconnected-(J3-JTAG3-PadA6)") (class "Default")
      (node (ref "J3") (pin "A6") (pinfunction "JTAG3_A6") (pintype "passive+no_connect"))
    )
    (net (code "57") (name "unconnected-(J3-JTAG4-PadA7)") (class "Default")
      (node (ref "J3") (pin "A7") (pinfunction "JTAG4_A7") (pintype "passive+no_connect"))
    )
    (net (code "58") (name "unconnected-(J3-JTAG5-PadA8)") (class "Default")
      (node (ref "J3") (pin "A8") (pinfunction "JTAG5_A8") (pintype "passive+no_connect"))
    )
    (net (code "59") (name "unconnected-(J3-RSVD-PadB12)") (class "Default")
      (node (ref "J3") (pin "B12") (pinfunction "RSVD_B12") (pintype "passive+no_connect"))
    )
    (net (code "60") (name "unconnected-(J4-CLKREQ#-Pad7)") (class "Default")
      (node (ref "J4") (pin "7") (pinfunction "CLKREQ#_7") (pintype "passive+no_connect"))
    )
    (net (code "61") (name "unconnected-(J4-Reserved_1-Pad3)") (class "Default")
      (node (ref "J4") (pin "3") (pinfunction "Reserved_1_3") (pintype "passive+no_connect"))
    )
    (net (code "62") (name "unconnected-(J4-Reserved_2-Pad5)") (class "Default")
      (node (ref "J4") (pin "5") (pinfunction "Reserved_2_5") (pintype "passive+no_connect"))
    )
    (net (code "63") (name "unconnected-(J4-Reserved_7-Pad45)") (class "Default")
      (node (ref "J4") (pin "45") (pinfunction "Reserved_7_45") (pintype "passive+no_connect"))
    )
    (net (code "64") (name "unconnected-(J4-Reserved_8-Pad47)") (class "Default")
      (node (ref "J4") (pin "47") (pinfunction "Reserved_8_47") (pintype "passive+no_connect"))
    )
    (net (code "65") (name "unconnected-(J4-Reserved_9-Pad49)") (class "Default")
      (node (ref "J4") (pin "49") (pinfunction "Reserved_9_49") (pintype "passive+no_connect"))
    )
    (net (code "66") (name "unconnected-(J4-Reserved_10-Pad51)") (class "Default")
      (node (ref "J4") (pin "51") (pinfunction "Reserved_10_51") (pintype "passive+no_connect"))
    )
    (net (code "67") (name "unconnected-(J4-Reserved{slash}UIM_C4-Pad19)") (class "Default")
      (node (ref "J4") (pin "19") (pinfunction "Reserved/UIM_C4_19") (pintype "passive+no_connect"))
    )
    (net (code "68") (name "unconnected-(J4-Reserved{slash}UIM_C8-Pad17)") (class "Default")
      (node (ref "J4") (pin "17") (pinfunction "Reserved/UIM_C8_17") (pintype "passive+no_connect"))
    )
    (net (code "69") (name "unconnected-(J5-CD1-PadS1)") (class "Default")
      (node (ref "J5") (pin "S1") (pinfunction "CD1_S1") (pintype "passive+no_connect"))
    )
    (net (code "70") (name "unconnected-(J5-CD2-PadS2)") (class "Default")
      (node (ref "J5") (pin "S2") (pinfunction "CD2_S2") (pintype "passive+no_connect"))
    )
  )
)
